# Sheet2.net
KiCad netlist of a schematic drawn in Altium Designer
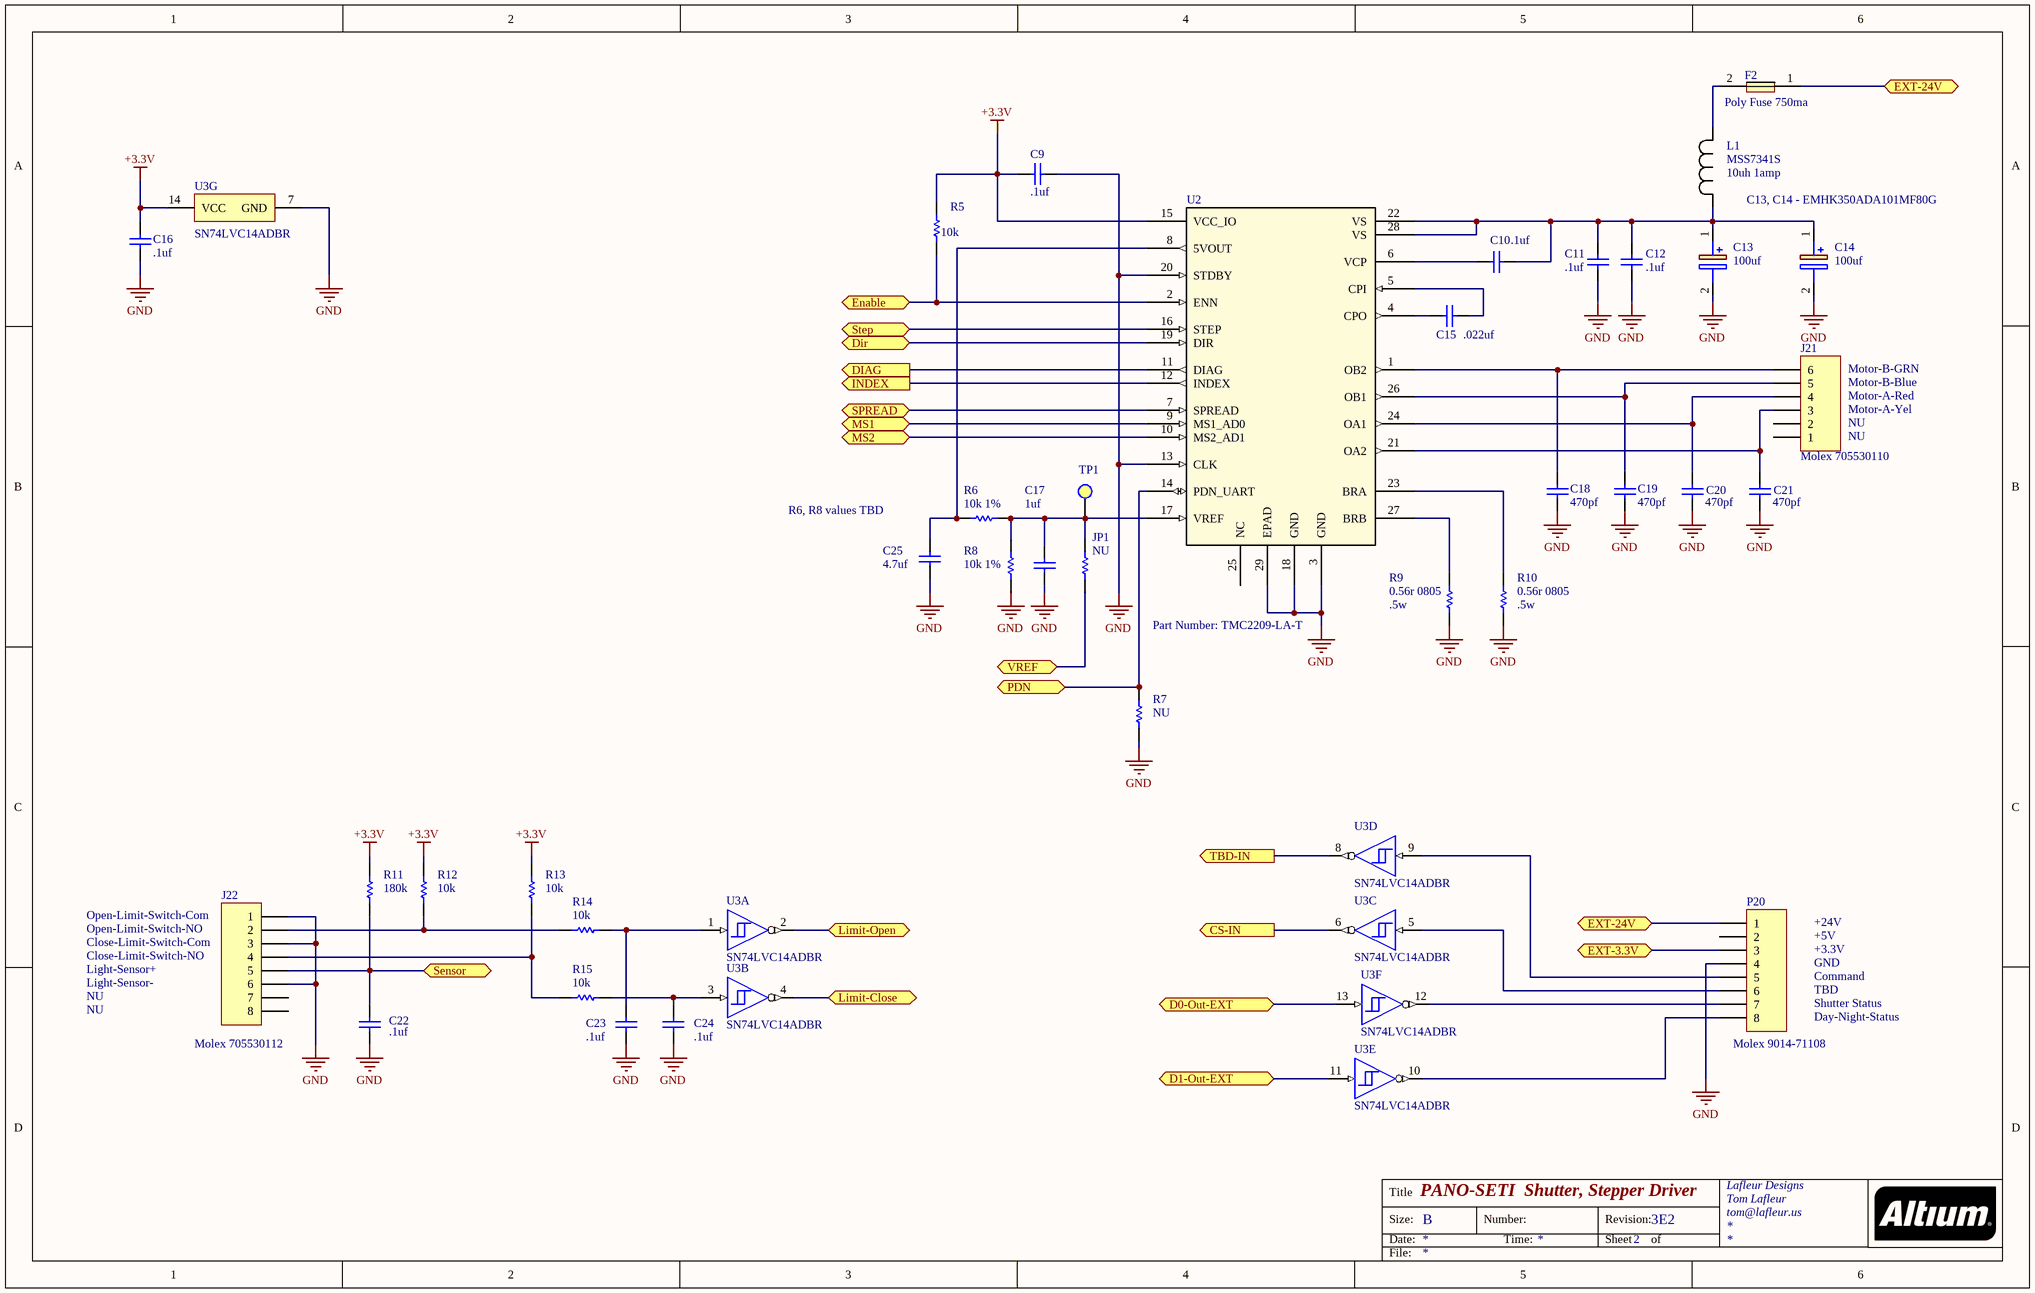
[diagram p0: Sheet2.SchDoc]

(export (version "E")
  (design (tool "Eeschema 10.0.6"))
  (components
    (comp (ref "C9")
      (value ".1uf")
      (footprint "6-0805")
      (description "Capacitor")
      (libsource (lib "Winmor-Demo-R2") (part "CAP_2"))
    )
    (comp (ref "C10")
      (value ".1uf")
      (footprint "6-0805")
      (description "Capacitor")
      (libsource (lib "Winmor-Demo-R2") (part "CAP_2"))
    )
    (comp (ref "C11")
      (value ".1uf")
      (footprint "6-0805")
      (description "Capacitor")
      (libsource (lib "Winmor-Demo-R2") (part "CAP_2"))
    )
    (comp (ref "C12")
      (value ".1uf")
      (footprint "6-0805")
      (description "Capacitor")
      (libsource (lib "Winmor-Demo-R2") (part "CAP_2"))
    )
    (comp (ref "C13")
      (value "100uf")
      (footprint "SamacSys:SMD_Lytic_F")
      (description "Capacitor Polarised")
      (fields
        (field (name "MANUFACTURER_PART_NUMBER") "EEE-HA1V101UP")
        (field (name "MOUSER PART NUMBER") "667-EEE-HA1V101UP")
      )
      (libsource (lib "*") (part "EEE-HA1V101UP"))
    )
    (comp (ref "C14")
      (value "100uf")
      (footprint "SamacSys:SMD_Lytic_F")
      (description "Capacitor Polarised")
      (fields
        (field (name "MANUFACTURER_PART_NUMBER") "EEE-HA1V101UP")
        (field (name "MOUSER PART NUMBER") "667-EEE-HA1V101UP")
      )
      (libsource (lib "*") (part "EEE-HA1V101UP"))
    )
    (comp (ref "C15")
      (value ".022uf")
      (footprint "6-0805")
      (description "Capacitor")
      (libsource (lib "Winmor-Demo-R2") (part "CAP_2"))
    )
    (comp (ref "C16")
      (value ".1uf")
      (footprint "6-0805")
      (description "Capacitor")
      (libsource (lib "Winmor-Demo-R2") (part "CAP_2"))
    )
    (comp (ref "C17")
      (value "1uf")
      (footprint "6-0805")
      (description "Capacitor")
      (libsource (lib "Winmor-Demo-R2") (part "CAP_2"))
    )
    (comp (ref "C18")
      (value "470pf")
      (footprint "6-0805")
      (description "Capacitor")
      (libsource (lib "Winmor-Demo-R2") (part "CAP_2"))
    )
    (comp (ref "C19")
      (value "470pf")
      (footprint "6-0805")
      (description "Capacitor")
      (libsource (lib "Winmor-Demo-R2") (part "CAP_2"))
    )
    (comp (ref "C20")
      (value "470pf")
      (footprint "6-0805")
      (description "Capacitor")
      (libsource (lib "Winmor-Demo-R2") (part "CAP_2"))
    )
    (comp (ref "C21")
      (value "470pf")
      (footprint "6-0805")
      (description "Capacitor")
      (libsource (lib "Winmor-Demo-R2") (part "CAP_2"))
    )
    (comp (ref "C22")
      (value ".1uf")
      (footprint "6-0805")
      (description "Capacitor")
      (libsource (lib "Winmor-Demo-R2") (part "CAP_2"))
    )
    (comp (ref "C23")
      (value ".1uf")
      (footprint "6-0805")
      (description "Capacitor")
      (libsource (lib "Winmor-Demo-R2") (part "CAP_2"))
    )
    (comp (ref "C24")
      (value ".1uf")
      (footprint "6-0805")
      (description "Capacitor")
      (libsource (lib "Winmor-Demo-R2") (part "CAP_2"))
    )
    (comp (ref "C25")
      (value "4.7uf")
      (footprint "6-0805")
      (description "Capacitor")
      (libsource (lib "Winmor-Demo-R2") (part "CAP_2"))
    )
    (comp (ref "F2")
      (value "Poly Fuse 750ma")
      (footprint "PTC 2016L")
      (description "Poly Fuse")
      (libsource (lib "N2K Project") (part "Poly Fuse"))
    )
    (comp (ref "J21")
      (value "Molex 705530110")
      (footprint "HDR1X6")
      (description "Header, 6-Pin")
      (fields (field (name "PUBLISHER") "Altium Limited"))
      (libsource (lib "Miscellaneous Connectors") (part "Header 6"))
    )
    (comp (ref "J22")
      (value "Molex 705530112")
      (footprint "HDR1X8")
      (description "Header, 8-Pin")
      (fields (field (name "PUBLISHER") "Altium Limited"))
      (libsource (lib "Miscellaneous Connectors") (part "Header 8"))
    )
    (comp (ref "JP1")
      (value "NU")
      (footprint "6-0805")
      (description "Precision Thick Film Chip Resistor, 10 Ohm to 2.2M Ohm Range, 1% Tolerance, 1206 Size, 0.125 W")
      (fields (field (name "PUBLISHER") "Altium Limited"))
      (libsource (lib "N2K Project") (part "ERJ8EN"))
    )
    (comp (ref "L1")
      (value "MSS7341S")
      (footprint "MSS7341502NLD")
      (description "No Description Available")
      (fields
        (field (name "MANUFACTURER_PART_NUMBER") "SRU1048-101Y")
        (field (name "COPYRIGHT") "Copyright (C) 2018 Accelerated Designs. All rights reserved")
      )
      (libsource (lib "2019-11-24_16-49-35") (part "SRU1048-101Y"))
    )
    (comp (ref "P20")
      (value "Molex 9014-71108")
      (footprint "HDR1X8")
      (description "Header, 8-Pin")
      (fields (field (name "PUBLISHER") "Altium Limited"))
      (libsource (lib "") (part "Header 8_1"))
    )
    (comp (ref "R5")
      (value "10k")
      (footprint "6-0805")
      (description "Precision Thick Film Chip Resistor, 10 Ohm to 2.2M Ohm Range, 1% Tolerance, 1206 Size, 0.125 W")
      (fields (field (name "PUBLISHER") "Altium Limited"))
      (libsource (lib "N2K Project") (part "ERJ8EN"))
    )
    (comp (ref "R6")
      (value "10k 1%")
      (footprint "6-0805")
      (description "Precision Thick Film Chip Resistor, 10 Ohm to 2.2M Ohm Range, 1% Tolerance, 1206 Size, 0.125 W")
      (fields (field (name "PUBLISHER") "Altium Limited"))
      (libsource (lib "N2K Project") (part "ERJ8EN"))
    )
    (comp (ref "R7")
      (value "NU")
      (footprint "6-0805")
      (description "Precision Thick Film Chip Resistor, 10 Ohm to 2.2M Ohm Range, 1% Tolerance, 1206 Size, 0.125 W")
      (fields (field (name "PUBLISHER") "Altium Limited"))
      (libsource (lib "N2K Project") (part "ERJ8EN"))
    )
    (comp (ref "R8")
      (value "10k 1%")
      (footprint "6-0805")
      (description "Precision Thick Film Chip Resistor, 10 Ohm to 2.2M Ohm Range, 1% Tolerance, 1206 Size, 0.125 W")
      (fields (field (name "PUBLISHER") "Altium Limited"))
      (libsource (lib "N2K Project") (part "ERJ8EN"))
    )
    (comp (ref "R9")
      (value "0.56r 0805")
      (footprint "6-0805")
      (description "Precision Thick Film Chip Resistor, 10 Ohm to 2.2M Ohm Range, 1% Tolerance, 1206 Size, 0.125 W")
      (fields (field (name "PUBLISHER") "Altium Limited"))
      (libsource (lib "N2K Project") (part "ERJ8EN"))
    )
    (comp (ref "R10")
      (value "0.56r 0805")
      (footprint "6-0805")
      (description "Precision Thick Film Chip Resistor, 10 Ohm to 2.2M Ohm Range, 1% Tolerance, 1206 Size, 0.125 W")
      (fields (field (name "PUBLISHER") "Altium Limited"))
      (libsource (lib "N2K Project") (part "ERJ8EN"))
    )
    (comp (ref "R11")
      (value "180k")
      (footprint "6-0805")
      (description "Precision Thick Film Chip Resistor, 10 Ohm to 2.2M Ohm Range, 1% Tolerance, 1206 Size, 0.125 W")
      (fields (field (name "PUBLISHER") "Altium Limited"))
      (libsource (lib "N2K Project") (part "ERJ8EN"))
    )
    (comp (ref "R12")
      (value "10k")
      (footprint "6-0805")
      (description "Precision Thick Film Chip Resistor, 10 Ohm to 2.2M Ohm Range, 1% Tolerance, 1206 Size, 0.125 W")
      (fields (field (name "PUBLISHER") "Altium Limited"))
      (libsource (lib "N2K Project") (part "ERJ8EN"))
    )
    (comp (ref "R13")
      (value "10k")
      (footprint "6-0805")
      (description "Precision Thick Film Chip Resistor, 10 Ohm to 2.2M Ohm Range, 1% Tolerance, 1206 Size, 0.125 W")
      (fields (field (name "PUBLISHER") "Altium Limited"))
      (libsource (lib "N2K Project") (part "ERJ8EN"))
    )
    (comp (ref "R14")
      (value "10k")
      (footprint "6-0805")
      (description "Precision Thick Film Chip Resistor, 10 Ohm to 2.2M Ohm Range, 1% Tolerance, 1206 Size, 0.125 W")
      (fields (field (name "PUBLISHER") "Altium Limited"))
      (libsource (lib "N2K Project") (part "ERJ8EN"))
    )
    (comp (ref "R15")
      (value "10k")
      (footprint "6-0805")
      (description "Precision Thick Film Chip Resistor, 10 Ohm to 2.2M Ohm Range, 1% Tolerance, 1206 Size, 0.125 W")
      (fields (field (name "PUBLISHER") "Altium Limited"))
      (libsource (lib "N2K Project") (part "ERJ8EN"))
    )
    (comp (ref "TP1")
      (value "TestPoint")
      (footprint "PCB111:Test Point-Thru-Hole")
      (libsource (lib "Seti-Controler-1a_1") (part "TestPoint"))
    )
    (comp (ref "U2")
      (value "Part Number: TMC2209-LA-T")
      (footprint "QFN50P500X500X90-29N")
      (description "No Description Available")
      (fields
        (field (name "MANUFACTURER_PART_NUMBER") "TMC2209-LA-T")
        (field (name "COPYRIGHT") "Copyright (C) 2018 Accelerated Designs. All rights reserved")
      )
      (libsource (lib "Seti-Controler-3") (part "TMC2209-LA-T"))
    )
    (comp (ref "U3")
      (value "SN74LVC14ADBR")
      (footprint "DB0014A_M")
      (description "Hex Schmitt-Trigger Inverter, DB0014A, LARGE T&R")
      (fields
        (field (name "GENERIC PART NUMBER") "SN74LVC14A")
        (field (name "MANUFACTURER") "Texas Instruments")
      )
      (libsource (lib "Altium Content Vault") (part "TI-CD_SNX4XXXXXX4X_19A-14-SCHMITT"))
    )
  )
  (nets
    (net (code "1") (name "+3.3V") (class "Default")
      (node (ref "C16") (pin "2") (pinfunction "2_2") (pintype "passive"))
      (node (ref "C9") (pin "1") (pinfunction "1_1") (pintype "passive"))
      (node (ref "R11") (pin "1") (pinfunction "1_1") (pintype "passive"))
      (node (ref "R12") (pin "1") (pinfunction "1_1") (pintype "passive"))
      (node (ref "R13") (pin "1") (pinfunction "1_1") (pintype "passive"))
      (node (ref "R5") (pin "1") (pinfunction "1_1") (pintype "passive"))
      (node (ref "U2") (pin "15") (pinfunction "VCC_IO_15") (pintype "power_in"))
      (node (ref "U3") (pin "14") (pinfunction "VCC_14") (pintype "power_in"))
    )
    (net (code "2") (name "/CS-IN") (class "Default")
      (node (ref "U3") (pin "6") (pinfunction "~{3Y}_6") (pintype "output"))
    )
    (net (code "3") (name "/D0-Out-EXT") (class "Default")
      (node (ref "U3") (pin "13") (pinfunction "6A_13") (pintype "input"))
    )
    (net (code "4") (name "/D1-Out-EXT") (class "Default")
      (node (ref "U3") (pin "11") (pinfunction "5A_11") (pintype "input"))
    )
    (net (code "5") (name "/DIAG") (class "Default")
      (node (ref "U2") (pin "11") (pinfunction "DIAG_11") (pintype "output"))
    )
    (net (code "6") (name "/Dir") (class "Default")
      (node (ref "U2") (pin "19") (pinfunction "DIR_19") (pintype "input"))
    )
    (net (code "7") (name "/EXT-3.3V") (class "Default")
      (node (ref "P20") (pin "3") (pinfunction "3_3") (pintype "passive"))
    )
    (net (code "8") (name "/EXT-24V") (class "Default")
      (node (ref "F2") (pin "1") (pinfunction "1_1") (pintype "passive"))
      (node (ref "P20") (pin "1") (pinfunction "1_1") (pintype "passive"))
    )
    (net (code "9") (name "/Enable") (class "Default")
      (node (ref "R5") (pin "2") (pinfunction "2_2") (pintype "passive"))
      (node (ref "U2") (pin "2") (pinfunction "ENN_2") (pintype "input"))
    )
    (net (code "10") (name "/INDEX") (class "Default")
      (node (ref "U2") (pin "12") (pinfunction "INDEX_12") (pintype "output"))
    )
    (net (code "11") (name "/Limit-Close") (class "Default")
      (node (ref "U3") (pin "4") (pinfunction "~{2Y}_4") (pintype "output"))
    )
    (net (code "12") (name "/Limit-Open") (class "Default")
      (node (ref "U3") (pin "2") (pinfunction "~{1Y}_2") (pintype "output"))
    )
    (net (code "13") (name "/MS1") (class "Default")
      (node (ref "U2") (pin "9") (pinfunction "MS1_AD0_9") (pintype "input"))
    )
    (net (code "14") (name "/MS2") (class "Default")
      (node (ref "U2") (pin "10") (pinfunction "MS2_AD1_10") (pintype "input"))
    )
    (net (code "15") (name "/PDN") (class "Default")
      (node (ref "R7") (pin "1") (pinfunction "1_1") (pintype "passive"))
      (node (ref "U2") (pin "14") (pinfunction "PDN_UART_14") (pintype "bidirectional"))
    )
    (net (code "16") (name "/SPREAD") (class "Default")
      (node (ref "U2") (pin "7") (pinfunction "SPREAD_7") (pintype "input"))
    )
    (net (code "17") (name "/Sensor") (class "Default")
      (node (ref "C22") (pin "2") (pinfunction "2_2") (pintype "passive"))
      (node (ref "J22") (pin "5") (pinfunction "5_5") (pintype "passive"))
      (node (ref "R11") (pin "2") (pinfunction "2_2") (pintype "passive"))
    )
    (net (code "18") (name "/Step") (class "Default")
      (node (ref "U2") (pin "16") (pinfunction "STEP_16") (pintype "input"))
    )
    (net (code "19") (name "/TBD-IN") (class "Default")
      (node (ref "U3") (pin "8") (pinfunction "~{4Y}_8") (pintype "output"))
    )
    (net (code "20") (name "/VREF") (class "Default")
      (node (ref "JP1") (pin "2") (pinfunction "2_2") (pintype "passive"))
    )
    (net (code "21") (name "GND") (class "Default")
      (node (ref "C11") (pin "2") (pinfunction "2_2") (pintype "passive"))
      (node (ref "C12") (pin "2") (pinfunction "2_2") (pintype "passive"))
      (node (ref "C13") (pin "2") (pinfunction "-_2") (pintype "passive"))
      (node (ref "C14") (pin "2") (pinfunction "-_2") (pintype "passive"))
      (node (ref "C16") (pin "1") (pinfunction "1_1") (pintype "passive"))
      (node (ref "C17") (pin "2") (pinfunction "2_2") (pintype "passive"))
      (node (ref "C18") (pin "2") (pinfunction "2_2") (pintype "passive"))
      (node (ref "C19") (pin "2") (pinfunction "2_2") (pintype "passive"))
      (node (ref "C20") (pin "2") (pinfunction "2_2") (pintype "passive"))
      (node (ref "C21") (pin "2") (pinfunction "2_2") (pintype "passive"))
      (node (ref "C22") (pin "1") (pinfunction "1_1") (pintype "passive"))
      (node (ref "C23") (pin "1") (pinfunction "1_1") (pintype "passive"))
      (node (ref "C24") (pin "1") (pinfunction "1_1") (pintype "passive"))
      (node (ref "C25") (pin "2") (pinfunction "2_2") (pintype "passive"))
      (node (ref "C9") (pin "2") (pinfunction "2_2") (pintype "passive"))
      (node (ref "J22") (pin "1") (pinfunction "1_1") (pintype "passive"))
      (node (ref "J22") (pin "3") (pinfunction "3_3") (pintype "passive"))
      (node (ref "J22") (pin "6") (pinfunction "6_6") (pintype "passive"))
      (node (ref "P20") (pin "4") (pinfunction "4_4") (pintype "passive"))
      (node (ref "R10") (pin "2") (pinfunction "2_2") (pintype "passive"))
      (node (ref "R7") (pin "2") (pinfunction "2_2") (pintype "passive"))
      (node (ref "R8") (pin "2") (pinfunction "2_2") (pintype "passive"))
      (node (ref "R9") (pin "2") (pinfunction "2_2") (pintype "passive"))
      (node (ref "U2") (pin "13") (pinfunction "CLK_13") (pintype "input"))
      (node (ref "U2") (pin "18") (pinfunction "GND_18") (pintype "power_in"))
      (node (ref "U2") (pin "20") (pinfunction "STDBY_20") (pintype "input"))
      (node (ref "U2") (pin "29") (pinfunction "EPAD_29") (pintype "passive"))
      (node (ref "U2") (pin "3") (pinfunction "GND_3") (pintype "power_in"))
      (node (ref "U3") (pin "7") (pinfunction "GND_7") (pintype "power_in"))
    )
    (net (code "22") (name "Net-(C13-+)") (class "Default")
      (node (ref "C10") (pin "2") (pinfunction "2_2") (pintype "passive"))
      (node (ref "C11") (pin "1") (pinfunction "1_1") (pintype "passive"))
      (node (ref "C12") (pin "1") (pinfunction "1_1") (pintype "passive"))
      (node (ref "C13") (pin "1") (pinfunction "+_1") (pintype "passive"))
      (node (ref "C14") (pin "1") (pinfunction "+_1") (pintype "passive"))
      (node (ref "L1") (pin "2") (pinfunction "2_2") (pintype "passive"))
      (node (ref "U2") (pin "22") (pinfunction "VS_22") (pintype "power_in"))
      (node (ref "U2") (pin "28") (pinfunction "VS_28") (pintype "power_in"))
    )
    (net (code "23") (name "Net-(F2-Pad2)") (class "Default")
      (node (ref "F2") (pin "2") (pinfunction "2_2") (pintype "passive"))
      (node (ref "L1") (pin "1") (pinfunction "1_1") (pintype "passive"))
    )
    (net (code "24") (name "Net-(J22-Pad2)") (class "Default")
      (node (ref "J22") (pin "2") (pinfunction "2_2") (pintype "passive"))
      (node (ref "R12") (pin "2") (pinfunction "2_2") (pintype "passive"))
      (node (ref "R14") (pin "1") (pinfunction "1_1") (pintype "passive"))
    )
    (net (code "25") (name "Net-(J22-Pad4)") (class "Default")
      (node (ref "J22") (pin "4") (pinfunction "4_4") (pintype "passive"))
      (node (ref "R13") (pin "2") (pinfunction "2_2") (pintype "passive"))
      (node (ref "R15") (pin "1") (pinfunction "1_1") (pintype "passive"))
    )
    (net (code "26") (name "Net-(TP1-TP?)") (class "Default")
      (node (ref "C17") (pin "1") (pinfunction "1_1") (pintype "passive"))
      (node (ref "JP1") (pin "1") (pinfunction "1_1") (pintype "passive"))
      (node (ref "R6") (pin "2") (pinfunction "2_2") (pintype "passive"))
      (node (ref "R8") (pin "1") (pinfunction "1_1") (pintype "passive"))
      (node (ref "TP1") (pin "1") (pinfunction "TP?_1") (pintype "passive"))
      (node (ref "U2") (pin "17") (pinfunction "VREF_17") (pintype "input"))
    )
    (net (code "27") (name "Net-(U2-5VOUT)") (class "Default")
      (node (ref "C25") (pin "1") (pinfunction "1_1") (pintype "passive"))
      (node (ref "R6") (pin "1") (pinfunction "1_1") (pintype "passive"))
      (node (ref "U2") (pin "8") (pinfunction "5VOUT_8") (pintype "output"))
    )
    (net (code "28") (name "Net-(U2-BRA)") (class "Default")
      (node (ref "R10") (pin "1") (pinfunction "1_1") (pintype "passive"))
      (node (ref "U2") (pin "23") (pinfunction "BRA_23") (pintype "passive"))
    )
    (net (code "29") (name "Net-(U2-BRB)") (class "Default")
      (node (ref "R9") (pin "1") (pinfunction "1_1") (pintype "passive"))
      (node (ref "U2") (pin "27") (pinfunction "BRB_27") (pintype "passive"))
    )
    (net (code "30") (name "Net-(U2-CPI)") (class "Default")
      (node (ref "C15") (pin "2") (pinfunction "2_2") (pintype "passive"))
      (node (ref "U2") (pin "5") (pinfunction "CPI_5") (pintype "input"))
    )
    (net (code "31") (name "Net-(U2-CPO)") (class "Default")
      (node (ref "C15") (pin "1") (pinfunction "1_1") (pintype "passive"))
      (node (ref "U2") (pin "4") (pinfunction "CPO_4") (pintype "output"))
    )
    (net (code "32") (name "Net-(U2-OA1)") (class "Default")
      (node (ref "C20") (pin "1") (pinfunction "1_1") (pintype "passive"))
      (node (ref "J21") (pin "4") (pinfunction "4_4") (pintype "passive"))
      (node (ref "U2") (pin "24") (pinfunction "OA1_24") (pintype "output"))
    )
    (net (code "33") (name "Net-(U2-OA2)") (class "Default")
      (node (ref "C21") (pin "1") (pinfunction "1_1") (pintype "passive"))
      (node (ref "J21") (pin "3") (pinfunction "3_3") (pintype "passive"))
      (node (ref "U2") (pin "21") (pinfunction "OA2_21") (pintype "output"))
    )
    (net (code "34") (name "Net-(U2-OB1)") (class "Default")
      (node (ref "C19") (pin "1") (pinfunction "1_1") (pintype "passive"))
      (node (ref "J21") (pin "5") (pinfunction "5_5") (pintype "passive"))
      (node (ref "U2") (pin "26") (pinfunction "OB1_26") (pintype "output"))
    )
    (net (code "35") (name "Net-(U2-OB2)") (class "Default")
      (node (ref "C18") (pin "1") (pinfunction "1_1") (pintype "passive"))
      (node (ref "J21") (pin "6") (pinfunction "6_6") (pintype "passive"))
      (node (ref "U2") (pin "1") (pinfunction "OB2_1") (pintype "output"))
    )
    (net (code "36") (name "Net-(U2-VCP)") (class "Default")
      (node (ref "C10") (pin "1") (pinfunction "1_1") (pintype "passive"))
      (node (ref "U2") (pin "6") (pinfunction "VCP_6") (pintype "power_in"))
    )
    (net (code "37") (name "Net-(U3A-1A)") (class "Default")
      (node (ref "C23") (pin "2") (pinfunction "2_2") (pintype "passive"))
      (node (ref "R14") (pin "2") (pinfunction "2_2") (pintype "passive"))
      (node (ref "U3") (pin "1") (pinfunction "1A_1") (pintype "input"))
    )
    (net (code "38") (name "Net-(U3B-2A)") (class "Default")
      (node (ref "C24") (pin "2") (pinfunction "2_2") (pintype "passive"))
      (node (ref "R15") (pin "2") (pinfunction "2_2") (pintype "passive"))
      (node (ref "U3") (pin "3") (pinfunction "2A_3") (pintype "input"))
    )
    (net (code "39") (name "Net-(U3C-3A)") (class "Default")
      (node (ref "P20") (pin "6") (pinfunction "6_6") (pintype "passive"))
      (node (ref "U3") (pin "5") (pinfunction "3A_5") (pintype "input"))
    )
    (net (code "40") (name "Net-(U3D-4A)") (class "Default")
      (node (ref "P20") (pin "5") (pinfunction "5_5") (pintype "passive"))
      (node (ref "U3") (pin "9") (pinfunction "4A_9") (pintype "input"))
    )
    (net (code "41") (name "Net-(U3E-~{5Y})") (class "Default")
      (node (ref "P20") (pin "8") (pinfunction "8_8") (pintype "passive"))
      (node (ref "U3") (pin "10") (pinfunction "~{5Y}_10") (pintype "output"))
    )
    (net (code "42") (name "Net-(U3F-~{6Y})") (class "Default")
      (node (ref "P20") (pin "7") (pinfunction "7_7") (pintype "passive"))
      (node (ref "U3") (pin "12") (pinfunction "~{6Y}_12") (pintype "output"))
    )
    (net (code "43") (name "unconnected-(J21-Pad1)") (class "Default")
      (node (ref "J21") (pin "1") (pinfunction "1_1") (pintype "passive"))
    )
    (net (code "44") (name "unconnected-(J21-Pad2)") (class "Default")
      (node (ref "J21") (pin "2") (pinfunction "2_2") (pintype "passive"))
    )
    (net (code "45") (name "unconnected-(J22-Pad7)") (class "Default")
      (node (ref "J22") (pin "7") (pinfunction "7_7") (pintype "passive"))
    )
    (net (code "46") (name "unconnected-(J22-Pad8)") (class "Default")
      (node (ref "J22") (pin "8") (pinfunction "8_8") (pintype "passive"))
    )
    (net (code "47") (name "unconnected-(P20-Pad2)") (class "Default")
      (node (ref "P20") (pin "2") (pinfunction "2_2") (pintype "passive"))
    )
    (net (code "48") (name "unconnected-(U2-NC-Pad25)") (class "Default")
      (node (ref "U2") (pin "25") (pinfunction "NC_25") (pintype "passive"))
    )
  )
)
